# MAIN.net
KiCad netlist of a schematic drawn in Altium Designer
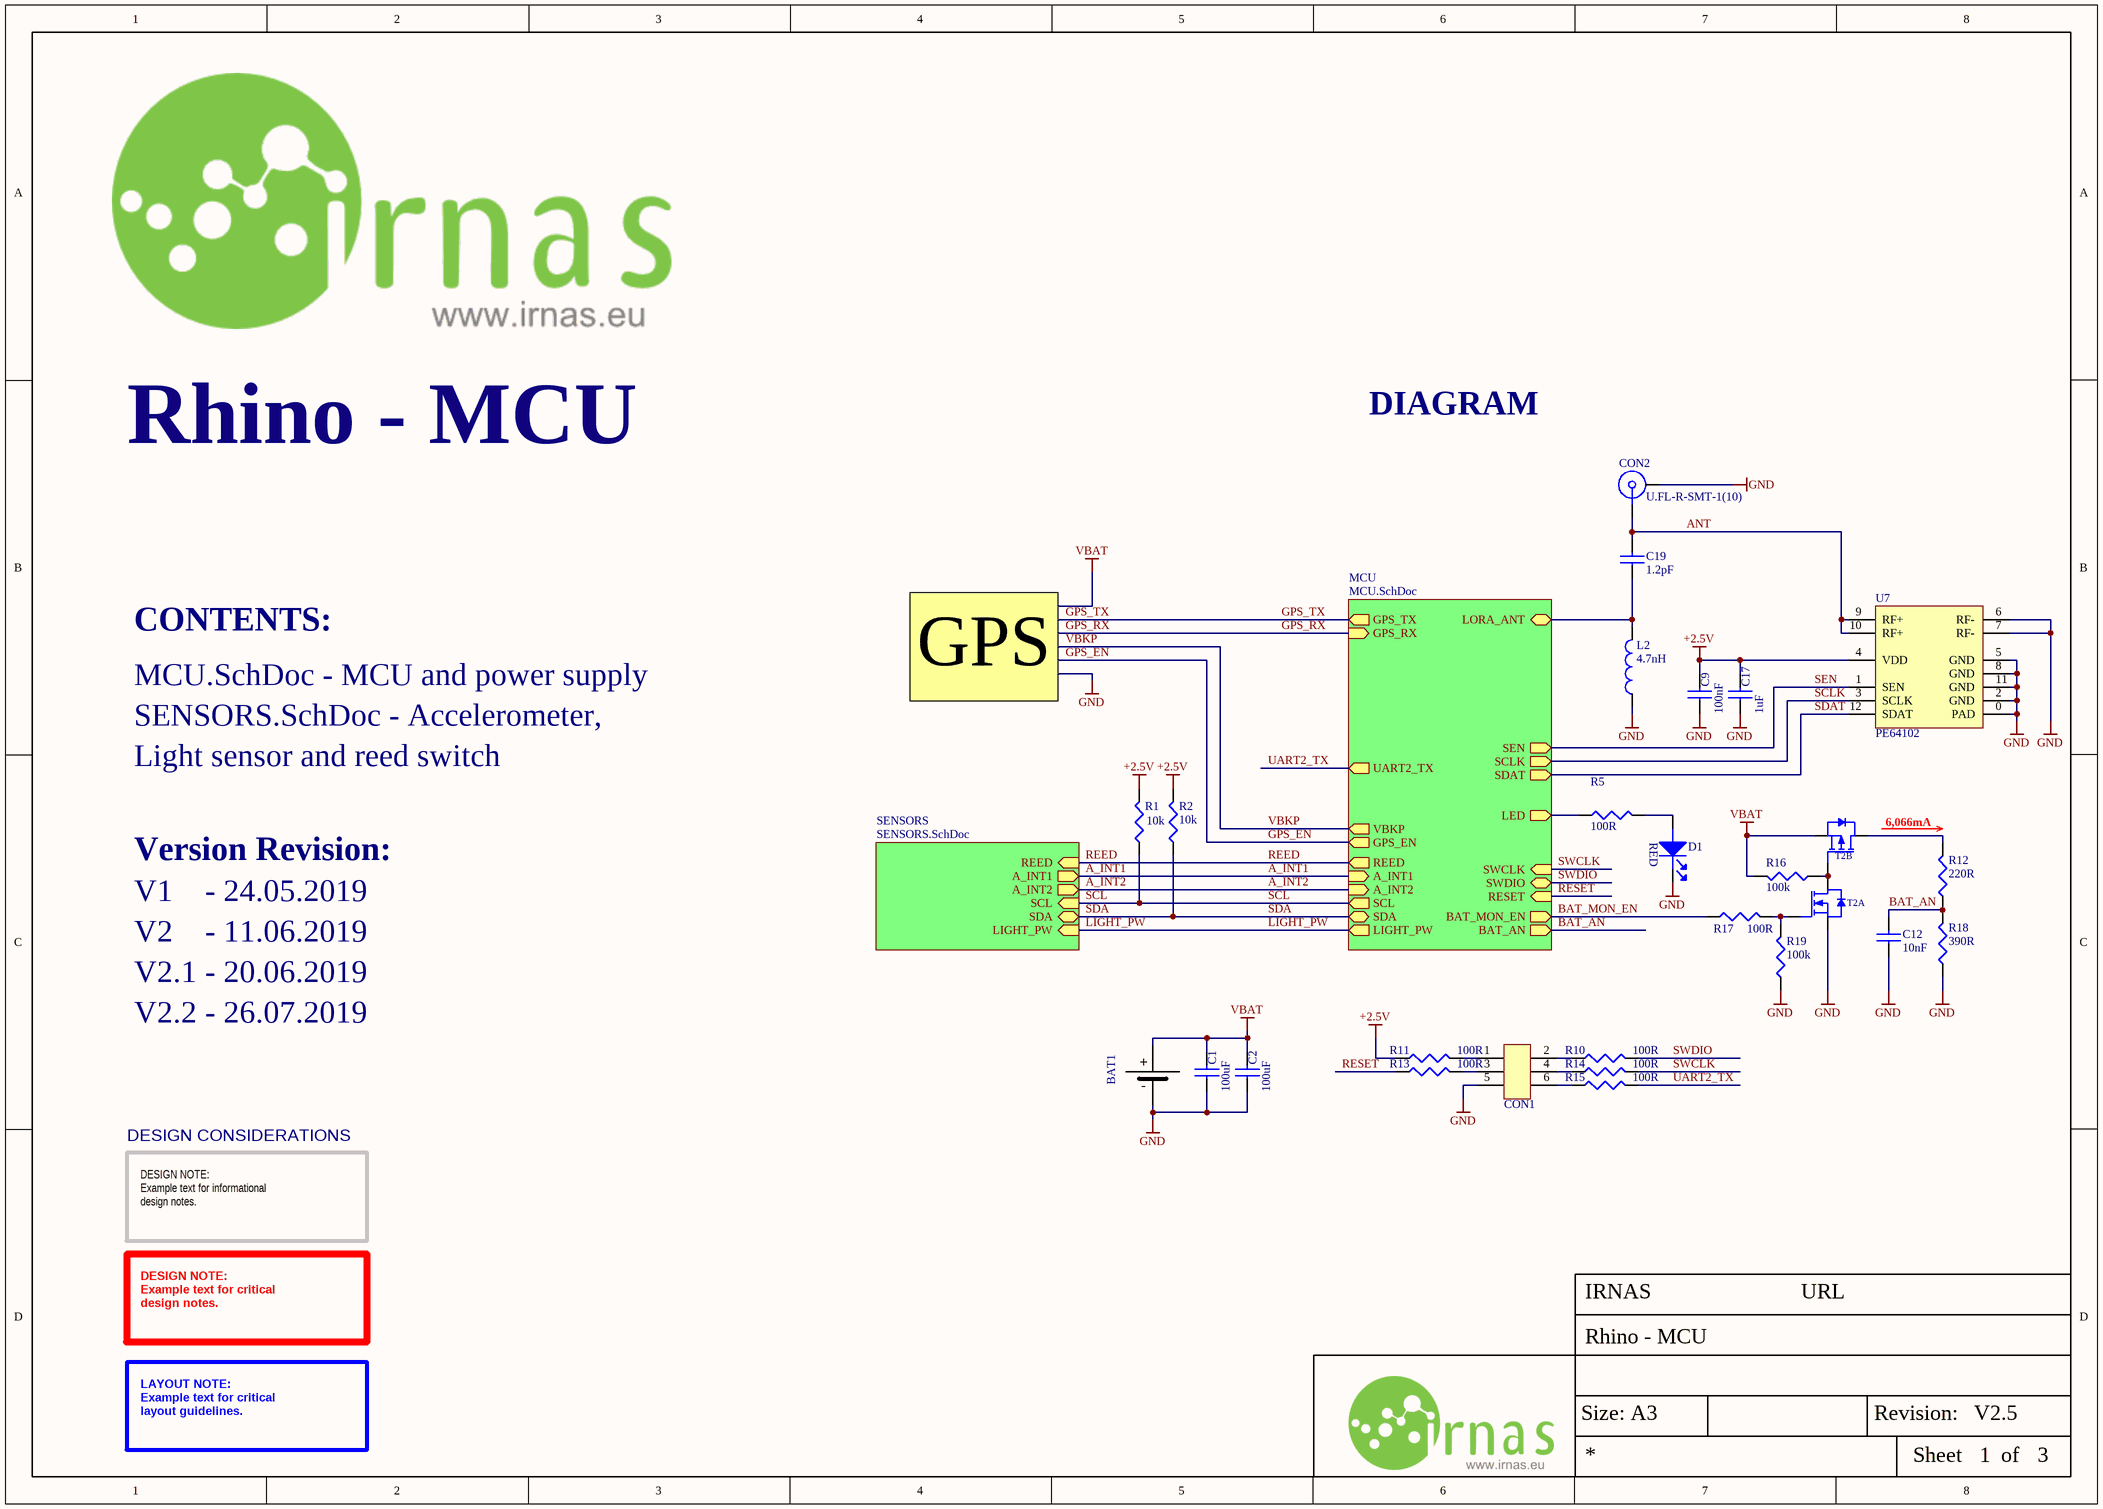
[diagram p0: MAIN.SchDoc]

(export (version "E")
  (design (tool "Eeschema 10.0.6"))
  (components
    (comp (ref "BAT1")
      (value "SAFT LS 14250PFR")
      (footprint "SAFT LS 14250PFR")
      (description "Battery: lithium; 3.6V; 1/2AA; 3pin,positive pole: 1pin; 1200mAh")
      (libsource (lib "Mechanical") (part "BAT - SAFT LS 14250PFR"))
    )
    (comp (ref "C1")
      (value "100uF")
      (footprint "CAP0805")
      (description "Multilayer Ceramic Capacitors MLCC - SMD/SMT 0805 100uF 4volts *Derate Voltage/Temp")
      (fields
        (field (name "MANUFACTURER") "Murata")
        (field (name "MANUFACTURER PART NUMBER") "GRM21BR60G107ME15L")
      )
      (libsource (lib "Passive") (part "C - 100uF/0805"))
    )
    (comp (ref "C2")
      (value "100uF")
      (footprint "CAP0805")
      (description "Multilayer Ceramic Capacitors MLCC - SMD/SMT 0805 100uF 4volts *Derate Voltage/Temp")
      (fields
        (field (name "MANUFACTURER") "Murata")
        (field (name "MANUFACTURER PART NUMBER") "GRM21BR60G107ME15L")
      )
      (libsource (lib "Passive") (part "C - 100uF/0805"))
    )
    (comp (ref "C9")
      (value "100nF")
      (footprint "CAP0402")
      (fields
        (field (name "MANUFACTURER") "Multicomp")
        (field (name "MANUFACTURER PART NUMBER") "MC0402X104J160CT")
        (field (name "TOLERANCE") "5%")
      )
      (libsource (lib "Passive") (part "C - 100nF/0402"))
    )
    (comp (ref "C12")
      (value "10nF")
      (footprint "CAP0402")
      (description "CAP CER 10000PF 16V X7R 0402")
      (fields
        (field (name "MANUFACTURER") "Murata")
        (field (name "MANUFACTURER PART NUMBER") "GRM155R71C103KA01D")
      )
      (libsource (lib "Passive") (part "C - 10nF/0402"))
    )
    (comp (ref "C17")
      (value "1uF")
      (footprint "CAP0402")
      (description "CAP CER 1UF 10V 20% X5R 0402")
      (fields
        (field (name "MANUFACTURER") "Murata")
        (field (name "MANUFACTURER PART NUMBER") "GRM155R61A105ME15D")
      )
      (libsource (lib "Passive") (part "C - 1uF/0402"))
    )
    (comp (ref "C19")
      (value "1.2pF")
      (footprint "CAP0402")
      (description "CAP CER 4700PF 50V X7R 0402")
      (fields
        (field (name "MANUFACTURER") "KEMET")
        (field (name "MANUFACTURER PART NUMBER") "C0402C472K5RAC-TU")
      )
      (libsource (lib "Passive") (part "C - 4.7nF/0402"))
    )
    (comp (ref "CON1")
      (value "Tag connect")
      (footprint "TC2030-IDC-NL")
      (libsource (lib "Connectors") (part "tag connecot 6 pin"))
    )
    (comp (ref "CON2")
      (value "U.FL-R-SMT-1(10)")
      (footprint "ufl connector smd")
      (description "RF / Coaxial Connector, U.FL Coaxial, Straight Jack, Surface Mount Vertical, 50 ohm, Brass")
      (fields (field (name "MANUFACTURER") "Hirose"))
      (libsource (lib "Connectors") (part "U.FL-R-SMT-1(10)"))
    )
    (comp (ref "D1")
      (value "LED RED")
      (footprint "LED0603")
      (description "BROADCOM LIMITED - HSMS-C190 - LED, RED, 10MCD, 626NM")
      (fields
        (field (name "MANUFACTURER") "BROADCOM LIMITED")
        (field (name "MANUFACTURER PART NUMBER") "HSMS-C190")
      )
      (libsource (lib "Active") (part "LED - LED RED"))
    )
    (comp (ref "L2")
      (value "4.7nH")
      (footprint "IND0402")
      (description "Inductor RF Chip Multi-Layer 4.3nH 0.3nH 100MHz 8Q-Factor Air 300mA 210mOhm DCR 0402 Paper T/R")
      (fields
        (field (name "MANUFACTURER") "Murata")
        (field (name "MANUFACTURER PART NUMBER") "LQG15HN4N3S02D")
      )
      (libsource (lib "Passive") (part "L - 4.3nH/0402"))
    )
    (comp (ref "R1")
      (value "10k")
      (footprint "RES0402")
      (fields
        (field (name "MANUFACTURER") "Multicomp")
        (field (name "MANUFACTURER PART NUMBER") "MCWR04X1002FTL")
        (field (name "TOLERANCE") "1%")
      )
      (libsource (lib "Passive") (part "R - 10k/0402"))
    )
    (comp (ref "R2")
      (value "10k")
      (footprint "RES0402")
      (fields
        (field (name "MANUFACTURER") "Multicomp")
        (field (name "MANUFACTURER PART NUMBER") "MCWR04X1002FTL")
        (field (name "TOLERANCE") "1%")
      )
      (libsource (lib "Passive") (part "R - 10k/0402"))
    )
    (comp (ref "R5")
      (value "100R")
      (footprint "RES0402")
      (fields
        (field (name "MANUFACTURER") "Multicomp")
        (field (name "MANUFACTURER PART NUMBER") "MCMR04X1000FTL")
        (field (name "TOLERANCE") "1%")
      )
      (libsource (lib "Passive") (part "R - 100R/0402"))
    )
    (comp (ref "R10")
      (value "100R")
      (footprint "RES0402")
      (fields
        (field (name "MANUFACTURER") "Multicomp")
        (field (name "MANUFACTURER PART NUMBER") "MCMR04X1000FTL")
        (field (name "TOLERANCE") "1%")
      )
      (libsource (lib "Passive") (part "R - 100R/0402"))
    )
    (comp (ref "R11")
      (value "100R")
      (footprint "RES0402")
      (fields
        (field (name "MANUFACTURER") "Multicomp")
        (field (name "MANUFACTURER PART NUMBER") "MCMR04X1000FTL")
        (field (name "TOLERANCE") "1%")
      )
      (libsource (lib "Passive") (part "R - 100R/0402"))
    )
    (comp (ref "R12")
      (value "220R")
      (footprint "RES0402")
      (description "SMD Chip Resistor, 0402 [1005 Metric], 220 ohm, CRCW e3 Series, 50 V, Thick Film, 63 mW")
      (fields (field (name "MANUFACTURER") "Multicomp") (field (name "IRNAS PART NO.") "/"))
      (libsource (lib "Passive") (part "R - 220R/0402"))
    )
    (comp (ref "R13")
      (value "100R")
      (footprint "RES0402")
      (fields
        (field (name "MANUFACTURER") "Multicomp")
        (field (name "MANUFACTURER PART NUMBER") "MCMR04X1000FTL")
        (field (name "TOLERANCE") "1%")
      )
      (libsource (lib "Passive") (part "R - 100R/0402"))
    )
    (comp (ref "R14")
      (value "100R")
      (footprint "RES0402")
      (fields
        (field (name "MANUFACTURER") "Multicomp")
        (field (name "MANUFACTURER PART NUMBER") "MCMR04X1000FTL")
        (field (name "TOLERANCE") "1%")
      )
      (libsource (lib "Passive") (part "R - 100R/0402"))
    )
    (comp (ref "R15")
      (value "100R")
      (footprint "RES0402")
      (fields
        (field (name "MANUFACTURER") "Multicomp")
        (field (name "MANUFACTURER PART NUMBER") "MCMR04X1000FTL")
        (field (name "TOLERANCE") "1%")
      )
      (libsource (lib "Passive") (part "R - 100R/0402"))
    )
    (comp (ref "R16")
      (value "100k")
      (footprint "RES0402")
      (description "MULTICOMP   MCWR04X1003FTL   RES, THICK FILM, 100KOHM, 1%, 0.0625W")
      (fields
        (field (name "MANUFACTURER") "Multicomp")
        (field (name "MANUFACTURER PART NUMBER") "MCWR04X1003FTL")
      )
      (libsource (lib "Passive") (part "R - 100k/0402"))
    )
    (comp (ref "R17")
      (value "100R")
      (footprint "RES0402")
      (fields
        (field (name "MANUFACTURER") "Multicomp")
        (field (name "MANUFACTURER PART NUMBER") "MCMR04X1000FTL")
        (field (name "TOLERANCE") "1%")
      )
      (libsource (lib "Passive") (part "R - 100R/0402"))
    )
    (comp (ref "R18")
      (value "390R")
      (footprint "RES0402")
      (description "SMD Chip Resistor, 0402 [1005 Metric], 390 ohm, MCWR Series, 50 V, Thick Film, 62.5 mW")
      (fields (field (name "MANUFACTURER") "Multicomp") (field (name "IRNAS PART NO.") "/"))
      (libsource (lib "Passive") (part "R - 390R/0402"))
    )
    (comp (ref "R19")
      (value "100k")
      (footprint "RES0402")
      (description "MULTICOMP   MCWR04X1003FTL   RES, THICK FILM, 100KOHM, 1%, 0.0625W")
      (fields
        (field (name "MANUFACTURER") "Multicomp")
        (field (name "MANUFACTURER PART NUMBER") "MCWR04X1003FTL")
      )
      (libsource (lib "Passive") (part "R - 100k/0402"))
    )
    (comp (ref "T2")
      (value "VT6M1T2CR")
      (footprint "VMT6")
      (description "Dual MOSFET, N and P Channel, 100 mA, 20 V, 2.5 ohm, 4.5 V, 1 V")
      (fields (field (name "AUTHOR") "Ciril Golob"))
      (libsource (lib "Active") (part "T_M - VT6M1T2CR"))
    )
    (comp (ref "U7")
      (value "PE64102")
      (footprint "QFN-12")
      (description "RF IC Digitally Tunable Capacitor General Purpose 100MHz ~ 3GHz SPI Interface 12-QFN (2x2)")
      (fields (field (name "MANUFACTURER") "u-blox") (field (name "MANUFACTURER PART NUMBER") "MAX-M8Q-0"))
      (libsource (lib "Active") (part "RF - PE64102"))
    )
  )
  (nets
    (net (code "1") (name "+2.5V") (class "Default")
      (node (ref "C17") (pin "2") (pinfunction "2_2") (pintype "passive"))
      (node (ref "C9") (pin "2") (pinfunction "2_2") (pintype "passive"))
      (node (ref "R1") (pin "2") (pinfunction "2_2") (pintype "passive"))
      (node (ref "R11") (pin "1") (pinfunction "1_1") (pintype "passive"))
      (node (ref "R2") (pin "2") (pinfunction "2_2") (pintype "passive"))
      (node (ref "U7") (pin "4") (pinfunction "VDD_4") (pintype "passive"))
    )
    (net (code "2") (name "/ANT") (class "Default")
      (node (ref "C19") (pin "2") (pinfunction "2_2") (pintype "passive"))
      (node (ref "CON2") (pin "1") (pinfunction "1_1") (pintype "open_collector"))
      (node (ref "U7") (pin "10") (pinfunction "RF+_10") (pintype "passive"))
      (node (ref "U7") (pin "9") (pinfunction "RF+_9") (pintype "passive"))
    )
    (net (code "5") (name "/BAT_AN") (class "Default")
      (node (ref "C12") (pin "2") (pinfunction "2_2") (pintype "passive"))
      (node (ref "R12") (pin "1") (pinfunction "1_1") (pintype "passive"))
      (node (ref "R18") (pin "2") (pinfunction "2_2") (pintype "passive"))
    )
    (net (code "6") (name "/BAT_MON_EN") (class "Default")
      (node (ref "R17") (pin "1") (pinfunction "1_1") (pintype "passive"))
    )
    (net (code "10") (name "/LED") (class "Default")
      (node (ref "R5") (pin "1") (pinfunction "1_1") (pintype "passive"))
    )
    (net (code "12") (name "/LORA_ANT") (class "Default")
      (node (ref "C19") (pin "1") (pinfunction "1_1") (pintype "passive"))
      (node (ref "L2") (pin "2") (pinfunction "2_2") (pintype "passive"))
    )
    (net (code "14") (name "/RESET") (class "Default")
      (node (ref "R13") (pin "1") (pinfunction "1_1") (pintype "passive"))
    )
    (net (code "15") (name "/SCL") (class "Default")
      (node (ref "R1") (pin "1") (pinfunction "1_1") (pintype "passive"))
    )
    (net (code "16") (name "/SCLK") (class "Default")
      (node (ref "U7") (pin "3") (pinfunction "SCLK_3") (pintype "passive"))
    )
    (net (code "17") (name "/SDA") (class "Default")
      (node (ref "R2") (pin "1") (pinfunction "1_1") (pintype "passive"))
    )
    (net (code "18") (name "/SDAT") (class "Default")
      (node (ref "U7") (pin "12") (pinfunction "SDAT_12") (pintype "passive"))
    )
    (net (code "19") (name "/SEN") (class "Default")
      (node (ref "U7") (pin "1") (pinfunction "SEN_1") (pintype "passive"))
    )
    (net (code "20") (name "/SWCLK") (class "Default")
      (node (ref "R14") (pin "2") (pinfunction "2_2") (pintype "passive"))
    )
    (net (code "21") (name "/SWDIO") (class "Default")
      (node (ref "R10") (pin "2") (pinfunction "2_2") (pintype "passive"))
    )
    (net (code "22") (name "/UART2_TX") (class "Default")
      (node (ref "R15") (pin "2") (pinfunction "2_2") (pintype "passive"))
    )
    (net (code "24") (name "GND") (class "Default")
      (node (ref "BAT1") (pin "1") (pinfunction "Negative_1") (pintype "passive"))
      (node (ref "C1") (pin "1") (pinfunction "1_1") (pintype "passive"))
      (node (ref "C12") (pin "1") (pinfunction "1_1") (pintype "passive"))
      (node (ref "C17") (pin "1") (pinfunction "1_1") (pintype "passive"))
      (node (ref "C2") (pin "1") (pinfunction "1_1") (pintype "passive"))
      (node (ref "C9") (pin "1") (pinfunction "1_1") (pintype "passive"))
      (node (ref "CON1") (pin "5") (pinfunction "5_5") (pintype "open_collector"))
      (node (ref "CON2") (pin "2") (pinfunction "2_2") (pintype "open_collector"))
      (node (ref "D1") (pin "1") (pinfunction "cathode_1") (pintype "passive"))
      (node (ref "L2") (pin "1") (pinfunction "1_1") (pintype "passive"))
      (node (ref "R18") (pin "1") (pinfunction "1_1") (pintype "passive"))
      (node (ref "R19") (pin "1") (pinfunction "1_1") (pintype "passive"))
      (node (ref "T2") (pin "1") (pinfunction "S1_1") (pintype "passive"))
      (node (ref "U7") (pin "0") (pinfunction "PAD_0") (pintype "passive"))
      (node (ref "U7") (pin "11") (pinfunction "GND_11") (pintype "passive"))
      (node (ref "U7") (pin "2") (pinfunction "GND_2") (pintype "passive"))
      (node (ref "U7") (pin "5") (pinfunction "GND_5") (pintype "passive"))
      (node (ref "U7") (pin "6") (pinfunction "RF-_6") (pintype "passive"))
      (node (ref "U7") (pin "7") (pinfunction "RF-_7") (pintype "passive"))
      (node (ref "U7") (pin "8") (pinfunction "GND_8") (pintype "passive"))
    )
    (net (code "25") (name "Net-(CON1-Pad1)") (class "Default")
      (node (ref "CON1") (pin "1") (pinfunction "1_1") (pintype "open_collector"))
      (node (ref "R11") (pin "2") (pinfunction "2_2") (pintype "passive"))
    )
    (net (code "26") (name "Net-(CON1-Pad2)") (class "Default")
      (node (ref "CON1") (pin "2") (pinfunction "2_2") (pintype "open_collector"))
      (node (ref "R10") (pin "1") (pinfunction "1_1") (pintype "passive"))
    )
    (net (code "27") (name "Net-(CON1-Pad3)") (class "Default")
      (node (ref "CON1") (pin "3") (pinfunction "3_3") (pintype "open_collector"))
      (node (ref "R13") (pin "2") (pinfunction "2_2") (pintype "passive"))
    )
    (net (code "28") (name "Net-(CON1-Pad4)") (class "Default")
      (node (ref "CON1") (pin "4") (pinfunction "4_4") (pintype "open_collector"))
      (node (ref "R14") (pin "1") (pinfunction "1_1") (pintype "passive"))
    )
    (net (code "29") (name "Net-(CON1-Pad6)") (class "Default")
      (node (ref "CON1") (pin "6") (pinfunction "6_6") (pintype "passive"))
      (node (ref "R15") (pin "1") (pinfunction "1_1") (pintype "passive"))
    )
    (net (code "30") (name "Net-(D1-ANODE)") (class "Default")
      (node (ref "D1") (pin "2") (pinfunction "ANODE_2") (pintype "passive"))
      (node (ref "R5") (pin "2") (pinfunction "2_2") (pintype "passive"))
    )
    (net (code "31") (name "Net-(T2A-D1)") (class "Default")
      (node (ref "R16") (pin "1") (pinfunction "1_1") (pintype "passive"))
      (node (ref "T2") (pin "5") (pinfunction "G2_5") (pintype "passive"))
      (node (ref "T2") (pin "6") (pinfunction "D1_6") (pintype "passive"))
    )
    (net (code "32") (name "Net-(T2A-G1)") (class "Default")
      (node (ref "R17") (pin "2") (pinfunction "2_2") (pintype "passive"))
      (node (ref "R19") (pin "2") (pinfunction "2_2") (pintype "passive"))
      (node (ref "T2") (pin "2") (pinfunction "G1_2") (pintype "passive"))
    )
    (net (code "33") (name "Net-(T2B-D2)") (class "Default")
      (node (ref "R12") (pin "2") (pinfunction "2_2") (pintype "passive"))
      (node (ref "T2") (pin "3") (pinfunction "D2_3") (pintype "passive"))
    )
    (net (code "34") (name "VBAT") (class "Default")
      (node (ref "BAT1") (pin "2") (pinfunction "Positive_2") (pintype "passive"))
      (node (ref "C1") (pin "2") (pinfunction "2_2") (pintype "passive"))
      (node (ref "C2") (pin "2") (pinfunction "2_2") (pintype "passive"))
      (node (ref "R16") (pin "2") (pinfunction "2_2") (pintype "passive"))
      (node (ref "T2") (pin "4") (pinfunction "S2_4") (pintype "passive"))
    )
  )
)
